# USB_and_LEDs.net
KiCad netlist of a schematic drawn in Altium Designer
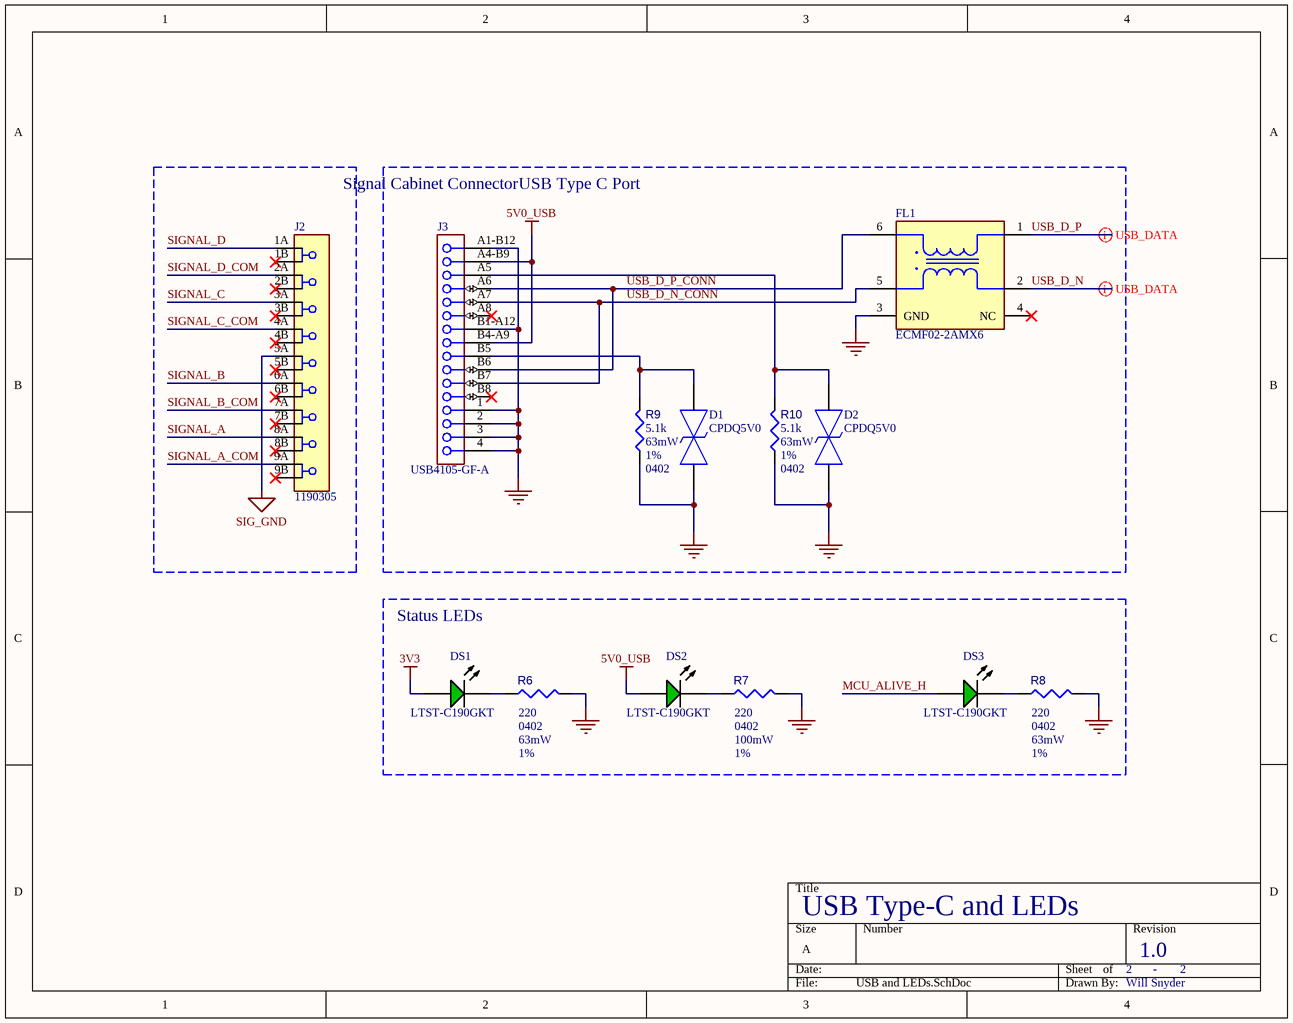
[diagram p0: USB and LEDs.SchDoc]

(export (version "E")
  (design (tool "Eeschema 10.0.6"))
  (components
    (comp (ref "D1")
      (value "CPDQ5V0")
      (footprint "MBTB-D-SOD-923F-IMP-0402")
      (description "18.6V Clamp 9.4A (8/20Âµs) Ipp Tvs Diode Surface Mount 0402/SOD-923F")
      (fields (field (name "MF") "Comchip Technology") (field (name "MP") "CPDQ5V0-HF"))
      (libsource (lib "Personal Workspace") (part "CPDQ5V0-HF"))
    )
    (comp (ref "D2")
      (value "CPDQ5V0")
      (footprint "MBTB-D-SOD-923F-IMP-0402")
      (description "18.6V Clamp 9.4A (8/20Âµs) Ipp Tvs Diode Surface Mount 0402/SOD-923F")
      (fields (field (name "MF") "Comchip Technology") (field (name "MP") "CPDQ5V0-HF"))
      (libsource (lib "Personal Workspace") (part "CPDQ5V0-HF"))
    )
    (comp (ref "DS1")
      (value "LTST-C190GKT")
      (footprint "LTST-C190GKT_V")
      (description "LED Uni-Color Green, 100 mW, 30 mA, -55 to 85 degC, 2-Pin SMD, RoHS, Tape and Reel")
      (fields (field (name "POWER") "100mW") (field (name "MANUFACTURER") "Lite-On"))
      (libsource (lib "Personal Workspace") (part "LED-GREEN-AK-2"))
    )
    (comp (ref "DS2")
      (value "LTST-C190GKT")
      (footprint "LTST-C190GKT_V")
      (description "LED Uni-Color Green, 100 mW, 30 mA, -55 to 85 degC, 2-Pin SMD, RoHS, Tape and Reel")
      (fields (field (name "POWER") "100mW") (field (name "MANUFACTURER") "Lite-On"))
      (libsource (lib "Personal Workspace") (part "LED-GREEN-AK-2"))
    )
    (comp (ref "DS3")
      (value "LTST-C190GKT")
      (footprint "LTST-C190GKT_V")
      (description "LED Uni-Color Green, 100 mW, 30 mA, -55 to 85 degC, 2-Pin SMD, RoHS, Tape and Reel")
      (fields (field (name "POWER") "100mW") (field (name "MANUFACTURER") "Lite-On"))
      (libsource (lib "Personal Workspace") (part "LED-GREEN-AK-2"))
    )
    (comp (ref "FL1")
      (value "ECMF02-2AMX6")
      (footprint "FP-QFN-6L-IPC_A")
      (description "Data Line Filter, 2 Function(s), 6 Pin(s), Plastic")
      (libsource (lib "Personal Workspace") (part "8feffc7f24acfb857157da90e949b57"))
    )
    (comp (ref "J2")
      (value "1190305")
      (footprint "PHOENIX_1190305")
      (description "LPT 2,5/ 9-5,0")
      (fields (field (name "MF") "Phoenix Contact"))
      (libsource (lib "Personal Workspace") (part "1190305"))
    )
    (comp (ref "J3")
      (value "USB4105-GF-A")
      (footprint "FP-USB4105-GF-A-MFG")
      (description "Conn USB 2.0 Type C RCP 24 POS 0.3mm/0.5mm Solder RA SMD 24 Terminal 1 Port T/R")
      (libsource (lib "Personal Workspace") (part "USB4105-GF-A"))
    )
    (comp (ref "R6")
      (value "220")
      (footprint "RESC1005X40X25NL05T05")
      (fields
        (field (name "TOLERANCE") "1%")
        (field (name "POWER") "63mW")
        (field (name "CASE/PACKAGE") "0402")
        (field (name "Comment") "CRCW040259R0FKED")
      )
      (libsource (lib "Personal Workspace") (part "RES-2"))
    )
    (comp (ref "R7")
      (value "220")
      (footprint "RESC1005X40X25NL05T05")
      (fields
        (field (name "CASE/PACKAGE") "0402")
        (field (name "TOLERANCE") "1%")
        (field (name "POWER") "100mW")
        (field (name "Comment") "ERJ-2RKF1430X")
      )
      (libsource (lib "Personal Workspace") (part "RES-2"))
    )
    (comp (ref "R8")
      (value "220")
      (footprint "RESC1005X40X25NL05T05")
      (fields
        (field (name "TOLERANCE") "1%")
        (field (name "POWER") "63mW")
        (field (name "CASE/PACKAGE") "0402")
        (field (name "Comment") "CRCW040259R0FKED")
      )
      (libsource (lib "Personal Workspace") (part "RES-2"))
    )
    (comp (ref "R9")
      (value "5.1k")
      (footprint "RESC1005X40X25NL05T05")
      (description "Fixed Resistor, Thin Film, 0.063W, 5100ohm, 50V, 1% +/-Tol, 50ppm/Cel, Surface Mount, 0402")
      (fields
        (field (name "POWER") "63mW")
        (field (name "TOLERANCE") "1%")
        (field (name "CASE/PACKAGE") "0402")
        (field (name "Comment") "MCS04020C5101FE000")
      )
      (libsource (lib "Personal Workspace") (part "RES-2"))
    )
    (comp (ref "R10")
      (value "5.1k")
      (footprint "RESC1005X40X25NL05T05")
      (description "Fixed Resistor, Thin Film, 0.063W, 5100ohm, 50V, 1% +/-Tol, 50ppm/Cel, Surface Mount, 0402")
      (fields
        (field (name "POWER") "63mW")
        (field (name "TOLERANCE") "1%")
        (field (name "CASE/PACKAGE") "0402")
        (field (name "Comment") "MCS04020C5101FE000")
      )
      (libsource (lib "Personal Workspace") (part "RES-2"))
    )
  )
  (nets
    (net (code "1") (name "/MCU_ALIVE_H") (class "Default")
      (node (ref "DS3") (pin "1") (pinfunction "A_1") (pintype "passive"))
    )
    (net (code "2") (name "/SIGNAL_A") (class "Default")
      (node (ref "J2") (pin "8A") (pinfunction "8A_8A") (pintype "passive"))
    )
    (net (code "3") (name "/SIGNAL_A_COM") (class "Default")
      (node (ref "J2") (pin "9A") (pinfunction "9A_9A") (pintype "passive"))
    )
    (net (code "4") (name "/SIGNAL_B") (class "Default")
      (node (ref "J2") (pin "6A") (pinfunction "6A_6A") (pintype "passive"))
    )
    (net (code "5") (name "/SIGNAL_B_COM") (class "Default")
      (node (ref "J2") (pin "7A") (pinfunction "7A_7A") (pintype "passive"))
    )
    (net (code "6") (name "/SIGNAL_C") (class "Default")
      (node (ref "J2") (pin "3A") (pinfunction "3A_3A") (pintype "passive"))
    )
    (net (code "7") (name "/SIGNAL_C_COM") (class "Default")
      (node (ref "J2") (pin "4A") (pinfunction "4A_4A") (pintype "passive"))
    )
    (net (code "8") (name "/SIGNAL_D") (class "Default")
      (node (ref "J2") (pin "1A") (pinfunction "1A_1A") (pintype "passive"))
    )
    (net (code "9") (name "/SIGNAL_D_COM") (class "Default")
      (node (ref "J2") (pin "2A") (pinfunction "2A_2A") (pintype "passive"))
    )
    (net (code "10") (name "/USB_D_N") (class "Default")
      (node (ref "FL1") (pin "2") (pinfunction "D-_2") (pintype "passive"))
    )
    (net (code "11") (name "/USB_D_N_CONN") (class "Default")
      (node (ref "FL1") (pin "5") (pinfunction "D-_5") (pintype "passive"))
      (node (ref "J3") (pin "A7") (pinfunction "Dn1_A7") (pintype "bidirectional"))
      (node (ref "J3") (pin "B7") (pinfunction "Dn2_B7") (pintype "bidirectional"))
    )
    (net (code "12") (name "/USB_D_P") (class "Default")
      (node (ref "FL1") (pin "1") (pinfunction "D+_1") (pintype "passive"))
    )
    (net (code "13") (name "/USB_D_P_CONN") (class "Default")
      (node (ref "FL1") (pin "6") (pinfunction "D+_6") (pintype "passive"))
      (node (ref "J3") (pin "A6") (pinfunction "Dp1_A6") (pintype "bidirectional"))
      (node (ref "J3") (pin "B6") (pinfunction "Dp2_B6") (pintype "bidirectional"))
    )
    (net (code "14") (name "3V3") (class "Default")
      (node (ref "DS1") (pin "1") (pinfunction "A_1") (pintype "passive"))
    )
    (net (code "15") (name "5V0_USB") (class "Default")
      (node (ref "DS2") (pin "1") (pinfunction "A_1") (pintype "passive"))
      (node (ref "J3") (pin "A4-B9") (pinfunction "VBUS_A4-B9") (pintype "power_in"))
      (node (ref "J3") (pin "B4-A9") (pinfunction "VBUS_B4-A9") (pintype "power_in"))
    )
    (net (code "16") (name "GND") (class "Default")
      (node (ref "D1") (pin "2") (pinfunction "A_2") (pintype "passive"))
      (node (ref "D2") (pin "2") (pinfunction "A_2") (pintype "passive"))
      (node (ref "FL1") (pin "3") (pinfunction "GND_3") (pintype "power_in"))
      (node (ref "J3") (pin "1") (pinfunction "MNT_1_1") (pintype "power_in"))
      (node (ref "J3") (pin "2") (pinfunction "MNT_2_2") (pintype "power_in"))
      (node (ref "J3") (pin "3") (pinfunction "MNT_3_3") (pintype "power_in"))
      (node (ref "J3") (pin "4") (pinfunction "MNT_4_4") (pintype "power_in"))
      (node (ref "J3") (pin "A1-B12") (pinfunction "GND_A1-B12") (pintype "power_in"))
      (node (ref "J3") (pin "B1-A12") (pinfunction "GND_B1-A12") (pintype "power_in"))
      (node (ref "R10") (pin "2") (pinfunction "2_2") (pintype "passive"))
      (node (ref "R6") (pin "2") (pinfunction "2_2") (pintype "passive"))
      (node (ref "R7") (pin "2") (pinfunction "2_2") (pintype "passive"))
      (node (ref "R8") (pin "2") (pinfunction "2_2") (pintype "passive"))
      (node (ref "R9") (pin "2") (pinfunction "2_2") (pintype "passive"))
    )
    (net (code "17") (name "Net-(D1-K)") (class "Default")
      (node (ref "D1") (pin "1") (pinfunction "K_1") (pintype "passive"))
      (node (ref "J3") (pin "B5") (pinfunction "CC2_B5") (pintype "passive"))
      (node (ref "R9") (pin "1") (pinfunction "1_1") (pintype "passive"))
    )
    (net (code "18") (name "Net-(D2-K)") (class "Default")
      (node (ref "D2") (pin "1") (pinfunction "K_1") (pintype "passive"))
      (node (ref "J3") (pin "A5") (pinfunction "CC1_A5") (pintype "passive"))
      (node (ref "R10") (pin "1") (pinfunction "1_1") (pintype "passive"))
    )
    (net (code "19") (name "Net-(DS1-K)") (class "Default")
      (node (ref "DS1") (pin "2") (pinfunction "K_2") (pintype "passive"))
      (node (ref "R6") (pin "1") (pinfunction "1_1") (pintype "passive"))
    )
    (net (code "20") (name "Net-(DS2-K)") (class "Default")
      (node (ref "DS2") (pin "2") (pinfunction "K_2") (pintype "passive"))
      (node (ref "R7") (pin "1") (pinfunction "1_1") (pintype "passive"))
    )
    (net (code "21") (name "Net-(DS3-K)") (class "Default")
      (node (ref "DS3") (pin "2") (pinfunction "K_2") (pintype "passive"))
      (node (ref "R8") (pin "1") (pinfunction "1_1") (pintype "passive"))
    )
    (net (code "22") (name "SIG_GND") (class "Default")
      (node (ref "J2") (pin "5A") (pinfunction "5A_5A") (pintype "passive"))
    )
    (net (code "23") (name "unconnected-(FL1-NC-Pad4)") (class "Default")
      (node (ref "FL1") (pin "4") (pinfunction "NC_4") (pintype "passive+no_connect"))
    )
    (net (code "24") (name "unconnected-(J2-Pad1B)") (class "Default")
      (node (ref "J2") (pin "1B") (pinfunction "1B_1B") (pintype "passive+no_connect"))
    )
    (net (code "25") (name "unconnected-(J2-Pad2B)") (class "Default")
      (node (ref "J2") (pin "2B") (pinfunction "2B_2B") (pintype "passive+no_connect"))
    )
    (net (code "26") (name "unconnected-(J2-Pad3B)") (class "Default")
      (node (ref "J2") (pin "3B") (pinfunction "3B_3B") (pintype "passive+no_connect"))
    )
    (net (code "27") (name "unconnected-(J2-Pad4B)") (class "Default")
      (node (ref "J2") (pin "4B") (pinfunction "4B_4B") (pintype "passive+no_connect"))
    )
    (net (code "28") (name "unconnected-(J2-Pad5B)") (class "Default")
      (node (ref "J2") (pin "5B") (pinfunction "5B_5B") (pintype "passive+no_connect"))
    )
    (net (code "29") (name "unconnected-(J2-Pad6B)") (class "Default")
      (node (ref "J2") (pin "6B") (pinfunction "6B_6B") (pintype "passive+no_connect"))
    )
    (net (code "30") (name "unconnected-(J2-Pad7B)") (class "Default")
      (node (ref "J2") (pin "7B") (pinfunction "7B_7B") (pintype "passive+no_connect"))
    )
    (net (code "31") (name "unconnected-(J2-Pad8B)") (class "Default")
      (node (ref "J2") (pin "8B") (pinfunction "8B_8B") (pintype "passive+no_connect"))
    )
    (net (code "32") (name "unconnected-(J2-Pad9B)") (class "Default")
      (node (ref "J2") (pin "9B") (pinfunction "9B_9B") (pintype "passive+no_connect"))
    )
    (net (code "33") (name "unconnected-(J3-SBU1-PadA8)") (class "Default")
      (node (ref "J3") (pin "A8") (pinfunction "SBU1_A8") (pintype "bidirectional+no_connect"))
    )
    (net (code "34") (name "unconnected-(J3-SBU2-PadB8)") (class "Default")
      (node (ref "J3") (pin "B8") (pinfunction "SBU2_B8") (pintype "bidirectional+no_connect"))
    )
  )
)
